# Sheet1.net
KiCad netlist of a schematic drawn in Altium Designer
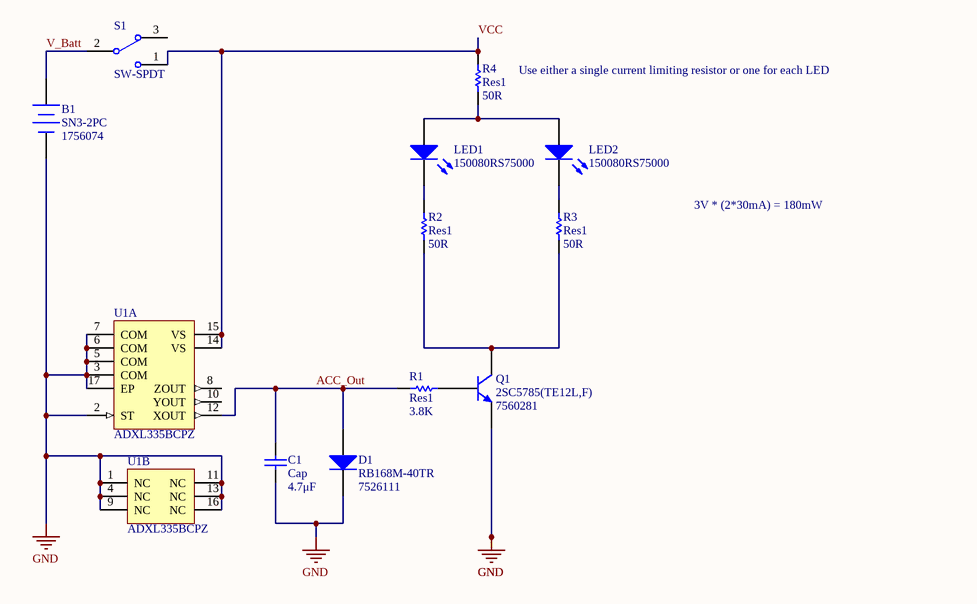
[diagram p0: Sheet1.SchDoc]

(export (version "E")
  (design (tool "Eeschema 10.0.6"))
  (components
    (comp (ref "B1")
      (value "SN3-2PC")
      (footprint "Battery Holder")
      (description "Battery Holder with Lead Wire / Pin / Snap Terminal")
      (fields (field (name "MANUFACTURER") "Takachi") (field (name "SUPPLIER PART NUMBER 1") "1756074"))
      (libsource (lib "Schlib1") (part "SN3-2PC"))
    )
    (comp (ref "C1")
      (value "Cap")
      (footprint "Capacitor 0603")
      (description "Capacitor")
      (fields (field (name "ALTIUM_VALUE") "4.7μF") (field (name "PUBLISHER") "Altium Limited"))
      (libsource (lib "Miscellaneous Devices") (part "Cap"))
    )
    (comp (ref "D1")
      (value "RB168M-40TR")
      (footprint "SODFL350X90-2N")
      (description "DIODE SCHOTTKY 40V 1A PMDU")
      (fields (field (name "MANUFACTURER") "Rohm") (field (name "SUPPLIER PART NUMBER 1") "7526111"))
      (libsource (lib "Schlib1") (part "RB168M-40TR"))
    )
    (comp (ref "LED1")
      (value "150080RS75000")
      (footprint "0805_A")
      (description "SMD mono-color Chip LED, WL-SMCW, Red")
      (fields (field (name "MANUFACTURER") "Wuerth Elektronik"))
      (libsource (lib "Altium Content Vault") (part "WE-LED_K1A2-2"))
    )
    (comp (ref "LED2")
      (value "150080RS75000")
      (footprint "0805_A")
      (description "SMD mono-color Chip LED, WL-SMCW, Red")
      (fields (field (name "MANUFACTURER") "Wuerth Elektronik"))
      (libsource (lib "Altium Content Vault") (part "WE-LED_K1A2-2"))
    )
    (comp (ref "Q1")
      (value "2SC5785(TE12L,F)")
      (footprint "SOT89-150P410X160-3N")
      (description "NPN Bipolar Transistor, 2 A, 10 V, 3-Pin SC-62")
      (fields (field (name "MANUFACTURER") "Toshiba") (field (name "SUPPLIER PART NUMBER 1") "7560281"))
      (libsource (lib "Schlib1") (part "2SC5785(TE12L,F)"))
    )
    (comp (ref "R1")
      (value "Res1")
      (footprint "Resistor 1206")
      (description "Resistor")
      (fields (field (name "ALTIUM_VALUE") "3.8K") (field (name "PUBLISHER") "Altium Limited"))
      (libsource (lib "Miscellaneous Devices") (part "Res1"))
    )
    (comp (ref "R2")
      (value "Res1")
      (footprint "Resistor 1206")
      (description "Resistor")
      (fields (field (name "ALTIUM_VALUE") "50R") (field (name "PUBLISHER") "Altium Limited"))
      (libsource (lib "Miscellaneous Devices") (part "Res1"))
    )
    (comp (ref "R3")
      (value "Res1")
      (footprint "Resistor 1206")
      (description "Resistor")
      (fields (field (name "ALTIUM_VALUE") "50R") (field (name "PUBLISHER") "Altium Limited"))
      (libsource (lib "Miscellaneous Devices") (part "Res1"))
    )
    (comp (ref "R4")
      (value "Res1")
      (footprint "Resistor 1206")
      (description "Resistor")
      (fields (field (name "ALTIUM_VALUE") "50R") (field (name "PUBLISHER") "Altium Limited"))
      (libsource (lib "Miscellaneous Devices") (part "Res1"))
    )
    (comp (ref "S1")
      (value "SW-SPDT")
      (footprint "JS202011SCQN Switch")
      (description "SPDT Subminiature Toggle Switch, Right Angle Mounting, Vertical Actuation")
      (fields (field (name "PUBLISHER") "Altium Limited"))
      (libsource (lib "Miscellaneous Devices") (part "SW-SPDT"))
    )
    (comp (ref "U1")
      (value "ADXL335BCPZ")
      (footprint "ADI-CP-16-14_L")
      (fields (field (name "MANUFACTURER") "Analog Devices"))
      (libsource (lib "Altium Content Vault") (part "ADI-ADXL3XX-CP-16-XX"))
    )
  )
  (nets
    (net (code "1") (name "/ACC_Out") (class "Default")
      (node (ref "C1") (pin "2") (pinfunction "2_2") (pintype "passive"))
      (node (ref "D1") (pin "1") (pinfunction "A_1") (pintype "passive"))
      (node (ref "R1") (pin "1") (pinfunction "1_1") (pintype "passive"))
      (node (ref "U1") (pin "12") (pinfunction "XOUT_12") (pintype "output"))
    )
    (net (code "2") (name "/VCC") (class "Default")
      (node (ref "R4") (pin "2") (pinfunction "2_2") (pintype "passive"))
      (node (ref "S1") (pin "1") (pinfunction "1_1") (pintype "passive"))
      (node (ref "U1") (pin "14") (pinfunction "VS_14") (pintype "power_in"))
      (node (ref "U1") (pin "15") (pinfunction "VS_15") (pintype "power_in"))
    )
    (net (code "3") (name "/V_Batt") (class "Default")
      (node (ref "B1") (pin "1") (pinfunction "+_1") (pintype "passive"))
      (node (ref "S1") (pin "2") (pinfunction "2_2") (pintype "passive"))
    )
    (net (code "4") (name "GND") (class "Default")
      (node (ref "B1") (pin "2") (pinfunction "-_2") (pintype "passive"))
      (node (ref "C1") (pin "1") (pinfunction "1_1") (pintype "passive"))
      (node (ref "D1") (pin "2") (pinfunction "K_2") (pintype "passive"))
      (node (ref "Q1") (pin "3") (pinfunction "E_3") (pintype "passive"))
      (node (ref "U1") (pin "1") (pinfunction "NC_1") (pintype "passive"))
      (node (ref "U1") (pin "11") (pinfunction "NC_11") (pintype "passive"))
      (node (ref "U1") (pin "13") (pinfunction "NC_13") (pintype "passive"))
      (node (ref "U1") (pin "16") (pinfunction "NC_16") (pintype "passive"))
      (node (ref "U1") (pin "17") (pinfunction "EP_17") (pintype "passive"))
      (node (ref "U1") (pin "2") (pinfunction "ST_2") (pintype "input"))
      (node (ref "U1") (pin "3") (pinfunction "COM_3") (pintype "power_in"))
      (node (ref "U1") (pin "4") (pinfunction "NC_4") (pintype "passive"))
      (node (ref "U1") (pin "5") (pinfunction "COM_5") (pintype "power_in"))
      (node (ref "U1") (pin "6") (pinfunction "COM_6") (pintype "power_in"))
      (node (ref "U1") (pin "7") (pinfunction "COM_7") (pintype "power_in"))
      (node (ref "U1") (pin "9") (pinfunction "NC_9") (pintype "passive"))
    )
    (net (code "5") (name "Net-(LED1-A)") (class "Default")
      (node (ref "LED1") (pin "2") (pinfunction "A_2") (pintype "passive"))
      (node (ref "LED2") (pin "2") (pinfunction "A_2") (pintype "passive"))
      (node (ref "R4") (pin "1") (pinfunction "1_1") (pintype "passive"))
    )
    (net (code "6") (name "Net-(LED1-K)") (class "Default")
      (node (ref "LED1") (pin "1") (pinfunction "K_1") (pintype "passive"))
      (node (ref "R2") (pin "2") (pinfunction "2_2") (pintype "passive"))
    )
    (net (code "7") (name "Net-(LED2-K)") (class "Default")
      (node (ref "LED2") (pin "1") (pinfunction "K_1") (pintype "passive"))
      (node (ref "R3") (pin "2") (pinfunction "2_2") (pintype "passive"))
    )
    (net (code "8") (name "Net-(Q1-B)") (class "Default")
      (node (ref "Q1") (pin "1") (pinfunction "B_1") (pintype "passive"))
      (node (ref "R1") (pin "2") (pinfunction "2_2") (pintype "passive"))
    )
    (net (code "9") (name "Net-(Q1-C)") (class "Default")
      (node (ref "Q1") (pin "2") (pinfunction "C_2") (pintype "passive"))
      (node (ref "R2") (pin "1") (pinfunction "1_1") (pintype "passive"))
      (node (ref "R3") (pin "1") (pinfunction "1_1") (pintype "passive"))
    )
    (net (code "10") (name "unconnected-(S1-Pad3)") (class "Default")
      (node (ref "S1") (pin "3") (pinfunction "3_3") (pintype "passive"))
    )
    (net (code "11") (name "unconnected-(U1A-YOUT-Pad10)") (class "Default")
      (node (ref "U1") (pin "10") (pinfunction "YOUT_10") (pintype "output"))
    )
    (net (code "12") (name "unconnected-(U1A-ZOUT-Pad8)") (class "Default")
      (node (ref "U1") (pin "8") (pinfunction "ZOUT_8") (pintype "output"))
    )
  )
)
